# GyroAccelHeaders.net
KiCad netlist of a schematic drawn in Altium Designer
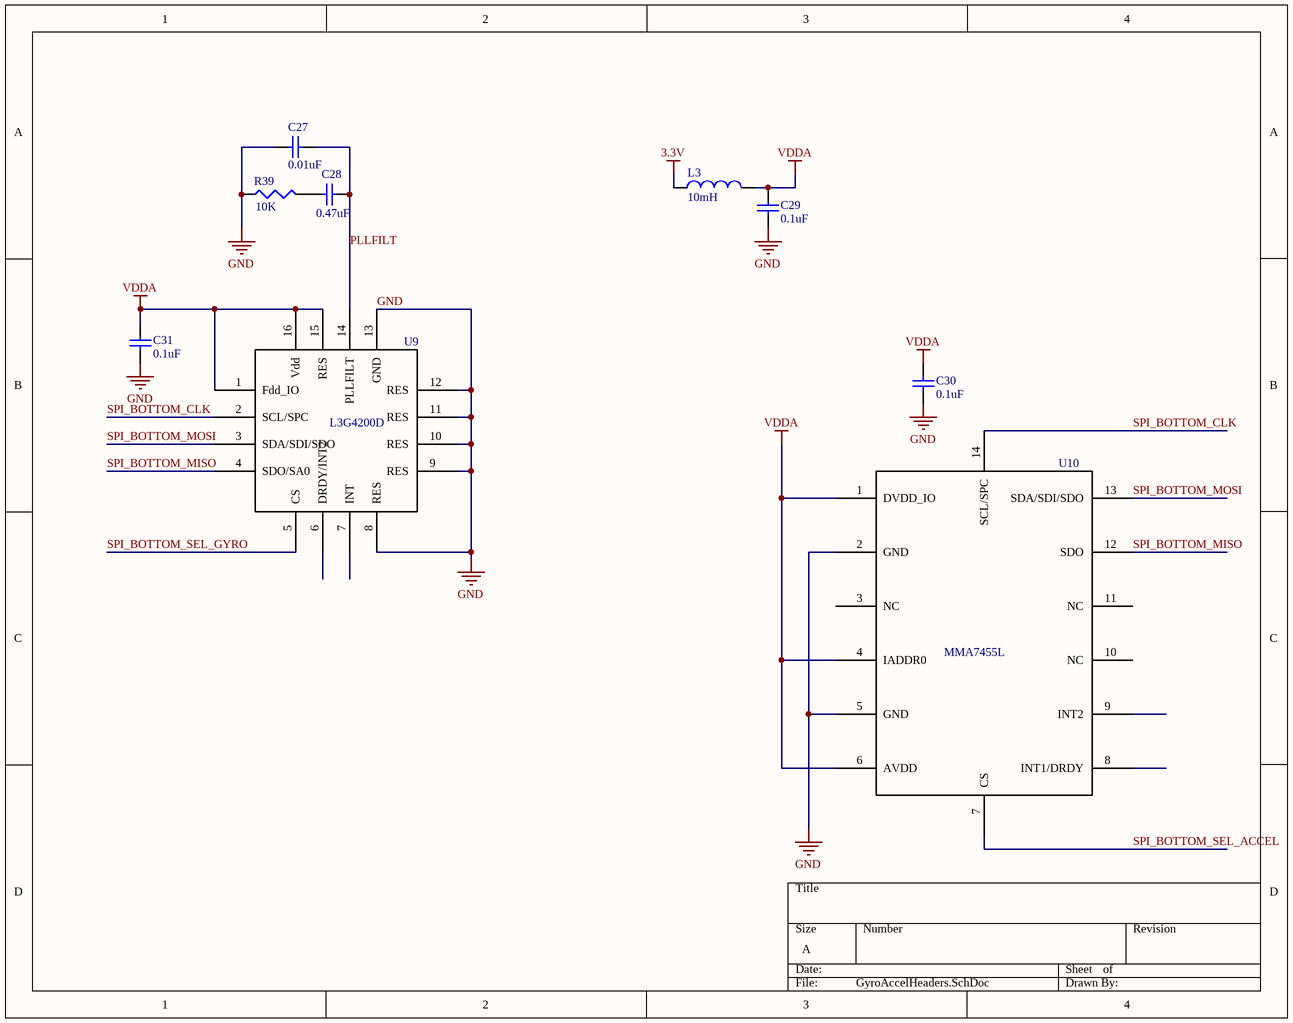
[diagram p0: GyroAccelHeaders.SchDoc]

(export (version "E")
  (design (tool "Eeschema 10.0.6"))
  (components
    (comp (ref "C27")
      (value "0.01uF")
      (footprint "CAPC1005L")
      (description "Capacitor (Semiconductor SIM Model)")
      (fields (field (name "Comment") "Cap Semi") (field (name "PUBLISHER") "Altium Limited"))
      (libsource (lib "Miscellaneous Devices") (part "Cap Semi"))
    )
    (comp (ref "C28")
      (value "0.47uF")
      (footprint "CAPC1005L")
      (description "Capacitor (Semiconductor SIM Model)")
      (fields (field (name "Comment") "Cap Semi") (field (name "PUBLISHER") "Altium Limited"))
      (libsource (lib "Miscellaneous Devices") (part "Cap Semi"))
    )
    (comp (ref "C29")
      (value "0.1uF")
      (footprint "CAPC1005L")
      (description "Capacitor (Semiconductor SIM Model)")
      (fields (field (name "Comment") "Cap Semi") (field (name "PUBLISHER") "Altium Limited"))
      (libsource (lib "Miscellaneous Devices") (part "Cap Semi"))
    )
    (comp (ref "C30")
      (value "0.1uF")
      (footprint "CAPC1005L")
      (description "Capacitor (Semiconductor SIM Model)")
      (fields (field (name "Comment") "Cap Semi") (field (name "PUBLISHER") "Altium Limited"))
      (libsource (lib "Miscellaneous Devices") (part "Cap Semi"))
    )
    (comp (ref "C31")
      (value "0.1uF")
      (footprint "CAPC1005L")
      (description "Capacitor (Semiconductor SIM Model)")
      (fields (field (name "Comment") "Cap Semi") (field (name "PUBLISHER") "Altium Limited"))
      (libsource (lib "Miscellaneous Devices") (part "Cap Semi"))
    )
    (comp (ref "L3")
      (value "10mH")
      (footprint "INDC2012L")
      (description "Inductor")
      (fields (field (name "PUBLISHER") "Altium Limited"))
      (libsource (lib "Miscellaneous Devices") (part "Inductor"))
    )
    (comp (ref "R39")
      (value "10K")
      (footprint "RESC1608L")
      (description "Resistor")
      (fields (field (name "Comment") "Res3") (field (name "PUBLISHER") "Altium Limited"))
      (libsource (lib "Miscellaneous Devices") (part "Res3"))
    )
    (comp (ref "U9")
      (value "L3G4200D")
      (footprint "L3G2004D")
      (description "3axis gyroscope, SPI")
      (libsource (lib "mrone") (part "L3G4200D"))
    )
    (comp (ref "U10")
      (value "MMA7455L")
      (footprint "MMA7455L")
      (description "3axis accelerometer")
      (libsource (lib "mrone") (part "MMA7455L"))
    )
  )
  (nets
    (net (code "1") (name "/PLLFILT") (class "Default")
      (node (ref "C27") (pin "1") (pinfunction "1_1") (pintype "passive"))
      (node (ref "C28") (pin "1") (pinfunction "1_1") (pintype "passive"))
      (node (ref "U9") (pin "14") (pinfunction "PLLFILT_14") (pintype "passive"))
    )
    (net (code "2") (name "/SPI_BOTTOM_CLK") (class "Default")
      (node (ref "U10") (pin "14") (pinfunction "SCL/SPC_14") (pintype "passive"))
      (node (ref "U9") (pin "2") (pinfunction "SCL/SPC_2") (pintype "passive"))
    )
    (net (code "3") (name "/SPI_BOTTOM_MISO") (class "Default")
      (node (ref "U10") (pin "12") (pinfunction "SDO_12") (pintype "passive"))
      (node (ref "U9") (pin "4") (pinfunction "SDO/SA0_4") (pintype "passive"))
    )
    (net (code "4") (name "/SPI_BOTTOM_MOSI") (class "Default")
      (node (ref "U10") (pin "13") (pinfunction "SDA/SDI/SDO_13") (pintype "passive"))
      (node (ref "U9") (pin "3") (pinfunction "SDA/SDI/SDO_3") (pintype "passive"))
    )
    (net (code "5") (name "/SPI_BOTTOM_SEL_ACCEL") (class "Default")
      (node (ref "U10") (pin "7") (pinfunction "CS_7") (pintype "passive"))
    )
    (net (code "6") (name "/SPI_BOTTOM_SEL_GYRO") (class "Default")
      (node (ref "U9") (pin "5") (pinfunction "CS_5") (pintype "passive"))
    )
    (net (code "7") (name "3.3V") (class "Default")
      (node (ref "L3") (pin "2") (pinfunction "2_2") (pintype "passive"))
    )
    (net (code "8") (name "GND") (class "Default")
      (node (ref "C27") (pin "2") (pinfunction "2_2") (pintype "passive"))
      (node (ref "C29") (pin "1") (pinfunction "1_1") (pintype "passive"))
      (node (ref "C30") (pin "1") (pinfunction "1_1") (pintype "passive"))
      (node (ref "C31") (pin "1") (pinfunction "1_1") (pintype "passive"))
      (node (ref "R39") (pin "1") (pinfunction "1_1") (pintype "passive"))
      (node (ref "U10") (pin "2") (pinfunction "GND_2") (pintype "passive"))
      (node (ref "U10") (pin "5") (pinfunction "GND_5") (pintype "passive"))
      (node (ref "U9") (pin "10") (pinfunction "RES_10") (pintype "passive"))
      (node (ref "U9") (pin "11") (pinfunction "RES_11") (pintype "passive"))
      (node (ref "U9") (pin "12") (pinfunction "RES_12") (pintype "passive"))
      (node (ref "U9") (pin "13") (pinfunction "GND_13") (pintype "passive"))
      (node (ref "U9") (pin "8") (pinfunction "RES_8") (pintype "passive"))
      (node (ref "U9") (pin "9") (pinfunction "RES_9") (pintype "passive"))
    )
    (net (code "9") (name "Net-(C28-Pad2)") (class "Default")
      (node (ref "C28") (pin "2") (pinfunction "2_2") (pintype "passive"))
      (node (ref "R39") (pin "2") (pinfunction "2_2") (pintype "passive"))
    )
    (net (code "10") (name "VDDA") (class "Default")
      (node (ref "C29") (pin "2") (pinfunction "2_2") (pintype "passive"))
      (node (ref "C30") (pin "2") (pinfunction "2_2") (pintype "passive"))
      (node (ref "C31") (pin "2") (pinfunction "2_2") (pintype "passive"))
      (node (ref "L3") (pin "1") (pinfunction "1_1") (pintype "passive"))
      (node (ref "U10") (pin "1") (pinfunction "DVDD_IO_1") (pintype "passive"))
      (node (ref "U10") (pin "4") (pinfunction "IADDR0_4") (pintype "passive"))
      (node (ref "U10") (pin "6") (pinfunction "AVDD_6") (pintype "passive"))
      (node (ref "U9") (pin "1") (pinfunction "Fdd_IO_1") (pintype "passive"))
      (node (ref "U9") (pin "15") (pinfunction "RES_15") (pintype "passive"))
      (node (ref "U9") (pin "16") (pinfunction "Vdd_16") (pintype "passive"))
    )
    (net (code "11") (name "unconnected-(U9-DRDY{slash}INT2-Pad6)") (class "Default")
      (node (ref "U9") (pin "6") (pinfunction "DRDY/INT2_6") (pintype "passive"))
    )
    (net (code "12") (name "unconnected-(U9-INT-Pad7)") (class "Default")
      (node (ref "U9") (pin "7") (pinfunction "INT_7") (pintype "passive"))
    )
    (net (code "13") (name "unconnected-(U10-INT1{slash}DRDY-Pad8)") (class "Default")
      (node (ref "U10") (pin "8") (pinfunction "INT1/DRDY_8") (pintype "passive"))
    )
    (net (code "14") (name "unconnected-(U10-INT2-Pad9)") (class "Default")
      (node (ref "U10") (pin "9") (pinfunction "INT2_9") (pintype "passive"))
    )
    (net (code "15") (name "unconnected-(U10-NC-Pad3)") (class "Default")
      (node (ref "U10") (pin "3") (pinfunction "NC_3") (pintype "passive"))
    )
    (net (code "16") (name "unconnected-(U10-NC-Pad10)") (class "Default")
      (node (ref "U10") (pin "10") (pinfunction "NC_10") (pintype "passive"))
    )
    (net (code "17") (name "unconnected-(U10-NC-Pad11)") (class "Default")
      (node (ref "U10") (pin "11") (pinfunction "NC_11") (pintype "passive"))
    )
  )
)
